# Sheet3-multi.net
KiCad netlist of a schematic drawn in Altium Designer
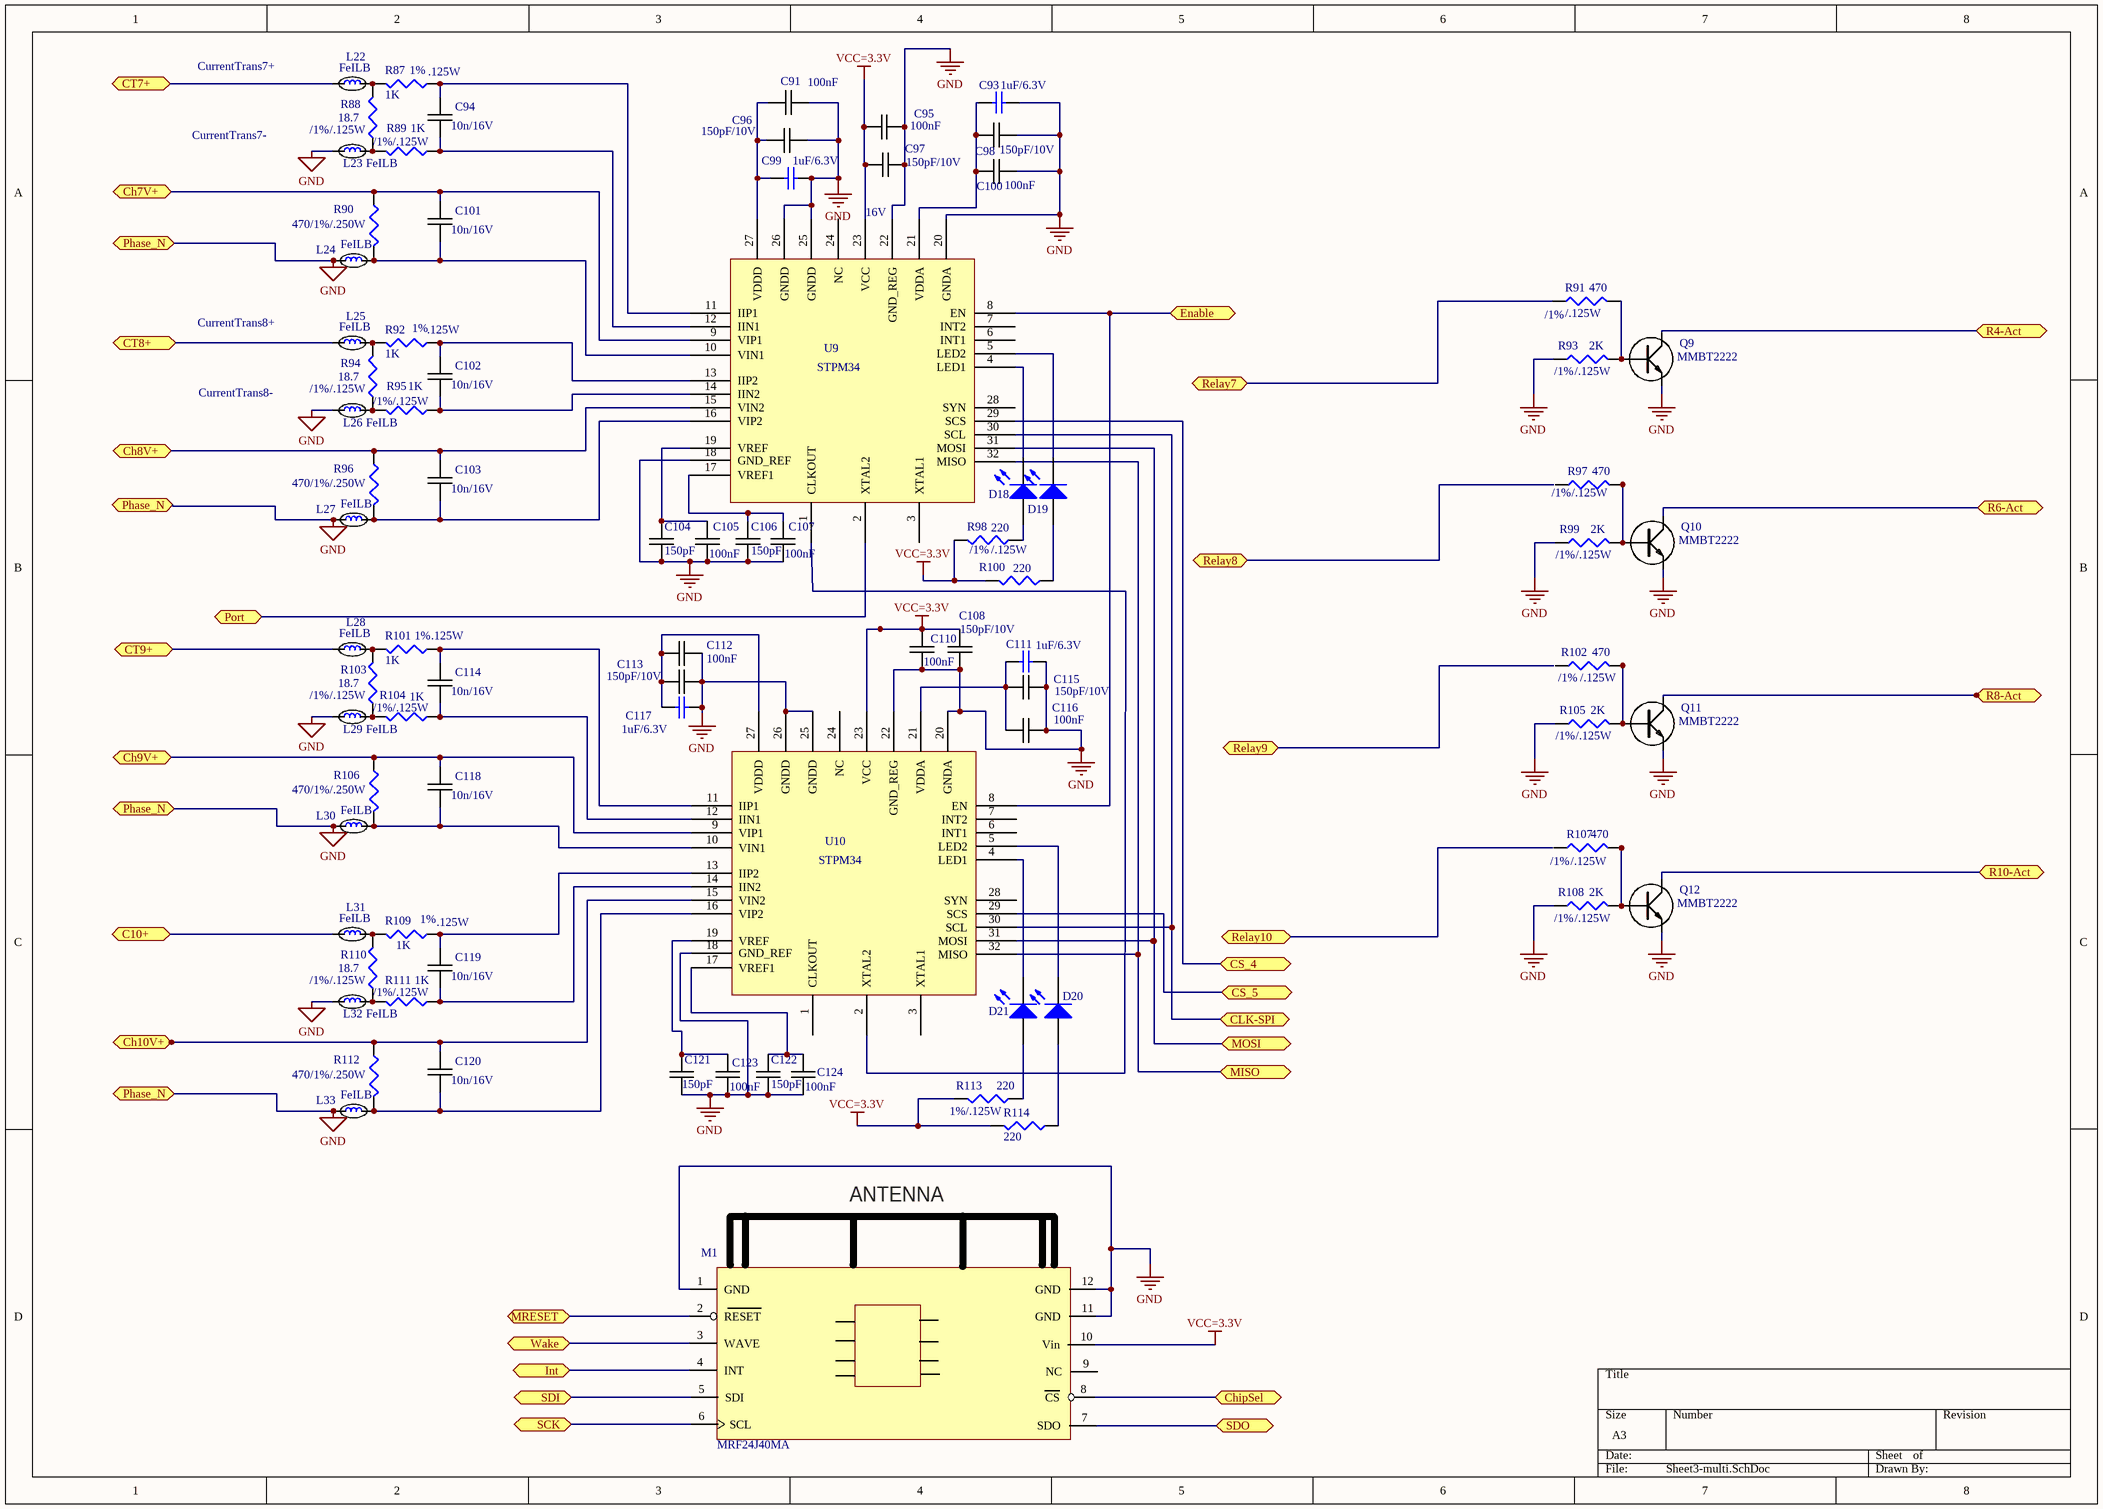
[diagram p0: Sheet3-multi.SchDoc]

(export (version "E")
  (design (tool "Eeschema 10.0.6"))
  (components
    (comp (ref "C91")
      (value "100nF")
      (footprint "0402C-GENERIC")
      (description "CAPACITOR 0805 CERAMIC")
      (fields (field (name "MANUFACTURER") "Taiyo Yuden"))
      (libsource (lib "vh_altium_library") (part "0805C-18PF-50V-C0G-JOH"))
    )
    (comp (ref "C93")
      (value "1uF/6.3V")
      (footprint "0402C-GENERIC")
      (description "Capacitor")
      (fields (field (name "MANUFACTURER") "Murata") (field (name "PUBLISHER") "Altium Limited"))
      (libsource (lib "Miscellaneous Devices") (part "Cap"))
    )
    (comp (ref "C94")
      (value "10n/16V")
      (footprint "0402C-GENERIC")
      (description "CAPACITOR 0805 CERAMIC")
      (fields (field (name "MANUFACTURER") "Murata Electronics"))
      (libsource (lib "vh_altium_library") (part "0805C-18PF-50V-C0G-JOH"))
    )
    (comp (ref "C95")
      (value "100nF")
      (footprint "0402C-GENERIC")
      (description "CAPACITOR 0805 CERAMIC")
      (fields (field (name "MANUFACTURER") "Taiyo Yuden"))
      (libsource (lib "vh_altium_library") (part "0805C-18PF-50V-C0G-JOH"))
    )
    (comp (ref "C96")
      (value "150pF/10V")
      (footprint "0402C-GENERIC")
      (description "CAPACITOR 0805 CERAMIC")
      (fields (field (name "MANUFACTURER") "Wurth Electronics"))
      (libsource (lib "vh_altium_library") (part "0805C-18PF-50V-C0G-JOH"))
    )
    (comp (ref "C97")
      (value "150pF/10V")
      (footprint "0402C-GENERIC")
      (description "CAPACITOR 0805 CERAMIC")
      (fields (field (name "MANUFACTURER") "Wurth Electronics"))
      (libsource (lib "vh_altium_library") (part "0805C-18PF-50V-C0G-JOH"))
    )
    (comp (ref "C98")
      (value "150pF/10V")
      (footprint "0402C-GENERIC")
      (description "CAPACITOR 0805 CERAMIC")
      (fields (field (name "MANUFACTURER") "Wurth Electronics"))
      (libsource (lib "vh_altium_library") (part "0805C-18PF-50V-C0G-JOH"))
    )
    (comp (ref "C99")
      (value "1uF/6.3V")
      (footprint "0402C-GENERIC")
      (description "Capacitor")
      (fields (field (name "MANUFACTURER") "Murata") (field (name "PUBLISHER") "Altium Limited"))
      (libsource (lib "Miscellaneous Devices") (part "Cap"))
    )
    (comp (ref "C100")
      (value "100nF")
      (footprint "0402C-GENERIC")
      (description "CAPACITOR 0805 CERAMIC")
      (fields (field (name "MANUFACTURER") "Taiyo Yuden"))
      (libsource (lib "vh_altium_library") (part "0805C-18PF-50V-C0G-JOH"))
    )
    (comp (ref "C101")
      (value "10n/16V")
      (footprint "0402C-GENERIC")
      (description "CAPACITOR 0805 CERAMIC")
      (fields (field (name "MANUFACTURER") "Murata Electronics"))
      (libsource (lib "vh_altium_library") (part "0805C-18PF-50V-C0G-JOH"))
    )
    (comp (ref "C102")
      (value "10n/16V")
      (footprint "0402C-GENERIC")
      (description "CAPACITOR 0805 CERAMIC")
      (fields (field (name "MANUFACTURER") "Murata Electronics"))
      (libsource (lib "vh_altium_library") (part "0805C-18PF-50V-C0G-JOH"))
    )
    (comp (ref "C103")
      (value "10n/16V")
      (footprint "0402C-GENERIC")
      (description "CAPACITOR 0805 CERAMIC")
      (fields (field (name "MANUFACTURER") "Murata Electronics"))
      (libsource (lib "vh_altium_library") (part "0805C-18PF-50V-C0G-JOH"))
    )
    (comp (ref "C104")
      (value "150pF")
      (footprint "0402C-GENERIC")
      (description "CAPACITOR 0805 CERAMIC")
      (fields (field (name "MANUFACTURER") "Wurth Electronics"))
      (libsource (lib "vh_altium_library") (part "0805C-18PF-50V-C0G-JOH"))
    )
    (comp (ref "C105")
      (value "100nF")
      (footprint "0402C-GENERIC")
      (description "CAPACITOR 0805 CERAMIC")
      (fields (field (name "MANUFACTURER") "Taiyo Yuden"))
      (libsource (lib "vh_altium_library") (part "0805C-18PF-50V-C0G-JOH"))
    )
    (comp (ref "C106")
      (value "150pF")
      (footprint "0402C-GENERIC")
      (description "CAPACITOR 0805 CERAMIC")
      (fields (field (name "MANUFACTURER") "Wurth Electronics"))
      (libsource (lib "vh_altium_library") (part "0805C-18PF-50V-C0G-JOH"))
    )
    (comp (ref "C107")
      (value "100nF")
      (footprint "0402C-GENERIC")
      (description "CAPACITOR 0805 CERAMIC")
      (fields (field (name "MANUFACTURER") "Taiyo Yuden"))
      (libsource (lib "vh_altium_library") (part "0805C-18PF-50V-C0G-JOH"))
    )
    (comp (ref "C108")
      (value "150pF/10V")
      (footprint "0402C-GENERIC")
      (description "CAPACITOR 0805 CERAMIC")
      (fields (field (name "MANUFACTURER") "Wurth Electronics"))
      (libsource (lib "vh_altium_library") (part "0805C-18PF-50V-C0G-JOH"))
    )
    (comp (ref "C110")
      (value "100nF")
      (footprint "0402C-GENERIC")
      (description "CAPACITOR 0805 CERAMIC")
      (fields (field (name "MANUFACTURER") "Taiyo Yuden"))
      (libsource (lib "vh_altium_library") (part "0805C-18PF-50V-C0G-JOH"))
    )
    (comp (ref "C111")
      (value "1uF/6.3V")
      (footprint "0402C-GENERIC")
      (description "Capacitor")
      (fields (field (name "MANUFACTURER") "Murata") (field (name "PUBLISHER") "Altium Limited"))
      (libsource (lib "Miscellaneous Devices") (part "Cap"))
    )
    (comp (ref "C112")
      (value "100nF")
      (footprint "0402C-GENERIC")
      (description "CAPACITOR 0805 CERAMIC")
      (fields (field (name "MANUFACTURER") "Taiyo Yuden"))
      (libsource (lib "vh_altium_library") (part "0805C-18PF-50V-C0G-JOH"))
    )
    (comp (ref "C113")
      (value "150pF/10V")
      (footprint "0402C-GENERIC")
      (description "CAPACITOR 0805 CERAMIC")
      (fields (field (name "MANUFACTURER") "Wurth Electronics"))
      (libsource (lib "vh_altium_library") (part "0805C-18PF-50V-C0G-JOH"))
    )
    (comp (ref "C114")
      (value "10n/16V")
      (footprint "0402C-GENERIC")
      (description "CAPACITOR 0805 CERAMIC")
      (fields (field (name "MANUFACTURER") "Murata Electronics"))
      (libsource (lib "vh_altium_library") (part "0805C-18PF-50V-C0G-JOH"))
    )
    (comp (ref "C115")
      (value "150pF/10V")
      (footprint "0402C-GENERIC")
      (description "CAPACITOR 0805 CERAMIC")
      (fields (field (name "MANUFACTURER") "Wurth Electronics"))
      (libsource (lib "vh_altium_library") (part "0805C-18PF-50V-C0G-JOH"))
    )
    (comp (ref "C116")
      (value "100nF")
      (footprint "0402C-GENERIC")
      (description "CAPACITOR 0805 CERAMIC")
      (fields (field (name "MANUFACTURER") "Taiyo Yuden"))
      (libsource (lib "vh_altium_library") (part "0805C-18PF-50V-C0G-JOH"))
    )
    (comp (ref "C117")
      (value "1uF/6.3V")
      (footprint "0402C-GENERIC")
      (description "Capacitor")
      (fields (field (name "MANUFACTURER") "Murata") (field (name "PUBLISHER") "Altium Limited"))
      (libsource (lib "Miscellaneous Devices") (part "Cap"))
    )
    (comp (ref "C118")
      (value "10n/16V")
      (footprint "0402C-GENERIC")
      (description "CAPACITOR 0805 CERAMIC")
      (fields (field (name "MANUFACTURER") "Murata Electronics"))
      (libsource (lib "vh_altium_library") (part "0805C-18PF-50V-C0G-JOH"))
    )
    (comp (ref "C119")
      (value "10n/16V")
      (footprint "0402C-GENERIC")
      (description "CAPACITOR 0805 CERAMIC")
      (fields (field (name "MANUFACTURER") "Murata Electronics"))
      (libsource (lib "vh_altium_library") (part "0805C-18PF-50V-C0G-JOH"))
    )
    (comp (ref "C120")
      (value "10n/16V")
      (footprint "0402C-GENERIC")
      (description "CAPACITOR 0805 CERAMIC")
      (fields (field (name "MANUFACTURER") "Murata Electronics"))
      (libsource (lib "vh_altium_library") (part "0805C-18PF-50V-C0G-JOH"))
    )
    (comp (ref "C121")
      (value "150pF")
      (footprint "0402C-GENERIC")
      (description "CAPACITOR 0805 CERAMIC")
      (fields (field (name "MANUFACTURER") "Wurth Electronics"))
      (libsource (lib "vh_altium_library") (part "0805C-18PF-50V-C0G-JOH"))
    )
    (comp (ref "C122")
      (value "150pF")
      (footprint "0402C-GENERIC")
      (description "CAPACITOR 0805 CERAMIC")
      (fields (field (name "MANUFACTURER") "Wurth Electronics"))
      (libsource (lib "vh_altium_library") (part "0805C-18PF-50V-C0G-JOH"))
    )
    (comp (ref "C123")
      (value "100nF")
      (footprint "0402C-GENERIC")
      (description "CAPACITOR 0805 CERAMIC")
      (fields (field (name "MANUFACTURER") "Taiyo Yuden"))
      (libsource (lib "vh_altium_library") (part "0805C-18PF-50V-C0G-JOH"))
    )
    (comp (ref "C124")
      (value "100nF")
      (footprint "0402C-GENERIC")
      (description "CAPACITOR 0805 CERAMIC")
      (fields (field (name "MANUFACTURER") "Taiyo Yuden"))
      (libsource (lib "vh_altium_library") (part "0805C-18PF-50V-C0G-JOH"))
    )
    (comp (ref "D18")
      (value "LED2")
      (footprint "LED-SM")
      (description "Typical RED, GREEN, YELLOW, AMBER GaAs LED")
      (fields (field (name "MANUFACTURER") "Lite-On Inc") (field (name "PUBLISHER") "Altium Limited"))
      (libsource (lib "Miscellaneous Devices") (part "LED2"))
    )
    (comp (ref "D19")
      (value "LED2")
      (footprint "LED-SM")
      (description "Typical RED, GREEN, YELLOW, AMBER GaAs LED")
      (fields (field (name "MANUFACTURER") "Lite-On Inc") (field (name "PUBLISHER") "Altium Limited"))
      (libsource (lib "Miscellaneous Devices") (part "LED2"))
    )
    (comp (ref "D20")
      (value "LED2")
      (footprint "LED-SM")
      (description "Typical RED, GREEN, YELLOW, AMBER GaAs LED")
      (fields (field (name "MANUFACTURER") "Lite-On Inc") (field (name "PUBLISHER") "Altium Limited"))
      (libsource (lib "Miscellaneous Devices") (part "LED2"))
    )
    (comp (ref "D21")
      (value "LED2")
      (footprint "LED-SM")
      (description "Typical RED, GREEN, YELLOW, AMBER GaAs LED")
      (fields (field (name "MANUFACTURER") "Lite-On Inc") (field (name "PUBLISHER") "Altium Limited"))
      (libsource (lib "Miscellaneous Devices") (part "LED2"))
    )
    (comp (ref "L22")
      (value "FeILB")
      (footprint "0603C-TBD")
      (fields (field (name "MANUFACTURER") "Brand Samsung"))
      (libsource (lib "SMLib") (part "FerrBeads/ILBB"))
    )
    (comp (ref "L23")
      (value "FeILB")
      (footprint "0603C-TBD")
      (fields (field (name "MANUFACTURER") "Brand Samsung"))
      (libsource (lib "SMLib") (part "FerrBeads/ILBB"))
    )
    (comp (ref "L24")
      (value "FeILB")
      (footprint "0603C-TBD")
      (fields (field (name "MANUFACTURER") "Brand Samsung"))
      (libsource (lib "SMLib") (part "FerrBeads/ILBB"))
    )
    (comp (ref "L25")
      (value "FeILB")
      (footprint "0603C-TBD")
      (fields (field (name "MANUFACTURER") "Brand Samsung"))
      (libsource (lib "SMLib") (part "FerrBeads/ILBB"))
    )
    (comp (ref "L26")
      (value "FeILB")
      (footprint "0603C-TBD")
      (fields (field (name "MANUFACTURER") "Brand Samsung"))
      (libsource (lib "SMLib") (part "FerrBeads/ILBB"))
    )
    (comp (ref "L27")
      (value "FeILB")
      (footprint "0603C-TBD")
      (fields (field (name "MANUFACTURER") "Brand Samsung"))
      (libsource (lib "SMLib") (part "FerrBeads/ILBB"))
    )
    (comp (ref "L28")
      (value "FeILB")
      (footprint "0603C-TBD")
      (fields (field (name "MANUFACTURER") "Brand Samsung"))
      (libsource (lib "SMLib") (part "FerrBeads/ILBB"))
    )
    (comp (ref "L29")
      (value "FeILB")
      (footprint "0603C-TBD")
      (fields (field (name "MANUFACTURER") "Brand Samsung"))
      (libsource (lib "SMLib") (part "FerrBeads/ILBB"))
    )
    (comp (ref "L30")
      (value "FeILB")
      (footprint "0603C-TBD")
      (fields (field (name "MANUFACTURER") "Brand Samsung"))
      (libsource (lib "SMLib") (part "FerrBeads/ILBB"))
    )
    (comp (ref "L31")
      (value "FeILB")
      (footprint "0603C-TBD")
      (fields (field (name "MANUFACTURER") "Brand Samsung"))
      (libsource (lib "SMLib") (part "FerrBeads/ILBB"))
    )
    (comp (ref "L32")
      (value "FeILB")
      (footprint "0603C-TBD")
      (fields (field (name "MANUFACTURER") "Brand Samsung"))
      (libsource (lib "SMLib") (part "FerrBeads/ILBB"))
    )
    (comp (ref "L33")
      (value "FeILB")
      (footprint "0603C-TBD")
      (fields (field (name "MANUFACTURER") "Brand Samsung"))
      (libsource (lib "SMLib") (part "FerrBeads/ILBB"))
    )
    (comp (ref "M1")
      (value "MRF24J40MA")
      (footprint "MRF24J40MA-zigBEE module")
      (fields (field (name "MANUFACTURER") "Microchip"))
      (libsource (lib "SMLib") (part "MRF24J40MA"))
    )
    (comp (ref "Q9")
      (value "MMBT2222")
      (footprint "MMBT2222")
      (description "BC847 SMALL SIGNAL NPN TRANSISTOR")
      (fields (field (name "MANUFACTURER") "Diodes  Inc."))
      (libsource (lib "vh_altium_library") (part "MMBT2222"))
    )
    (comp (ref "Q10")
      (value "MMBT2222")
      (footprint "MMBT2222")
      (description "BC847 SMALL SIGNAL NPN TRANSISTOR")
      (fields (field (name "MANUFACTURER") "Diodes  Inc."))
      (libsource (lib "vh_altium_library") (part "MMBT2222"))
    )
    (comp (ref "Q11")
      (value "MMBT2222")
      (footprint "MMBT2222")
      (description "BC847 SMALL SIGNAL NPN TRANSISTOR")
      (fields (field (name "MANUFACTURER") "Diodes  Inc."))
      (libsource (lib "vh_altium_library") (part "MMBT2222"))
    )
    (comp (ref "Q12")
      (value "MMBT2222")
      (footprint "MMBT2222")
      (description "BC847 SMALL SIGNAL NPN TRANSISTOR")
      (fields (field (name "MANUFACTURER") "Diodes  Inc."))
      (libsource (lib "vh_altium_library") (part "MMBT2222"))
    )
    (comp (ref "R87")
      (value "1K")
      (footprint "0402R-TBD")
      (description "Resistor")
      (fields (field (name "MANUFACTURER") "Panasonic") (field (name "PUBLISHER") "Altium Limited"))
      (libsource (lib "Miscellaneous Devices") (part "Res3"))
    )
    (comp (ref "R88")
      (value "18.7")
      (footprint "0402R-TBD")
      (description "Resistor")
      (fields (field (name "MANUFACTURER") "Panasonic") (field (name "PUBLISHER") "Altium Limited"))
      (libsource (lib "Miscellaneous Devices") (part "Res3"))
    )
    (comp (ref "R89")
      (value "1K")
      (footprint "0402R-TBD")
      (description "Resistor")
      (fields (field (name "MANUFACTURER") "Panasonic") (field (name "PUBLISHER") "Altium Limited"))
      (libsource (lib "Miscellaneous Devices") (part "Res3"))
    )
    (comp (ref "R90")
      (value "470/1%/.250W")
      (footprint "1206FB-GENERIC")
      (description "Resistor")
      (fields (field (name "MANUFACTURER") "Panasonic Co") (field (name "PUBLISHER") "Altium Limited"))
      (libsource (lib "Miscellaneous Devices") (part "Res3"))
    )
    (comp (ref "R91")
      (value "470")
      (footprint "0402R-TBD")
      (description "Resistor")
      (fields (field (name "MANUFACTURER") "Panasonic") (field (name "PUBLISHER") "Altium Limited"))
      (libsource (lib "Miscellaneous Devices") (part "Res3"))
    )
    (comp (ref "R92")
      (value "1K")
      (footprint "0402R-TBD")
      (description "Resistor")
      (fields (field (name "MANUFACTURER") "Panasonic") (field (name "PUBLISHER") "Altium Limited"))
      (libsource (lib "Miscellaneous Devices") (part "Res3"))
    )
    (comp (ref "R93")
      (value "2K")
      (footprint "0402R-TBD")
      (description "Resistor")
      (fields (field (name "MANUFACTURER") "Panasonic") (field (name "PUBLISHER") "Altium Limited"))
      (libsource (lib "Miscellaneous Devices") (part "Res3"))
    )
    (comp (ref "R94")
      (value "18.7")
      (footprint "0402R-TBD")
      (description "Resistor")
      (fields (field (name "MANUFACTURER") "Panasonic") (field (name "PUBLISHER") "Altium Limited"))
      (libsource (lib "Miscellaneous Devices") (part "Res3"))
    )
    (comp (ref "R95")
      (value "1K")
      (footprint "0402R-TBD")
      (description "Resistor")
      (fields (field (name "MANUFACTURER") "Panasonic") (field (name "PUBLISHER") "Altium Limited"))
      (libsource (lib "Miscellaneous Devices") (part "Res3"))
    )
    (comp (ref "R96")
      (value "470/1%/.250W")
      (footprint "1206FB-GENERIC")
      (description "Resistor")
      (fields (field (name "MANUFACTURER") "Panasonic Co") (field (name "PUBLISHER") "Altium Limited"))
      (libsource (lib "Miscellaneous Devices") (part "Res3"))
    )
    (comp (ref "R97")
      (value "470")
      (footprint "0402R-TBD")
      (description "Resistor")
      (fields (field (name "MANUFACTURER") "Panasonic") (field (name "PUBLISHER") "Altium Limited"))
      (libsource (lib "Miscellaneous Devices") (part "Res3"))
    )
    (comp (ref "R98")
      (value "220")
      (footprint "0402C-TBD")
      (description "Resistor")
      (fields (field (name "MANUFACTURER") "Panasonic") (field (name "PUBLISHER") "Altium Limited"))
      (libsource (lib "Miscellaneous Devices") (part "Res3"))
    )
    (comp (ref "R99")
      (value "2K")
      (footprint "0402R-TBD")
      (description "Resistor")
      (fields (field (name "MANUFACTURER") "Panasonic") (field (name "PUBLISHER") "Altium Limited"))
      (libsource (lib "Miscellaneous Devices") (part "Res3"))
    )
    (comp (ref "R100")
      (value "220")
      (footprint "0402C-TBD")
      (description "Resistor")
      (fields (field (name "MANUFACTURER") "Panasonic") (field (name "PUBLISHER") "Altium Limited"))
      (libsource (lib "Miscellaneous Devices") (part "Res3"))
    )
    (comp (ref "R101")
      (value "1K")
      (footprint "0402R-TBD")
      (description "Resistor")
      (fields (field (name "MANUFACTURER") "Panasonic") (field (name "PUBLISHER") "Altium Limited"))
      (libsource (lib "Miscellaneous Devices") (part "Res3"))
    )
    (comp (ref "R102")
      (value "470")
      (footprint "0402R-TBD")
      (description "Resistor")
      (fields (field (name "MANUFACTURER") "Panasonic") (field (name "PUBLISHER") "Altium Limited"))
      (libsource (lib "Miscellaneous Devices") (part "Res3"))
    )
    (comp (ref "R103")
      (value "18.7")
      (footprint "0402R-TBD")
      (description "Resistor")
      (fields (field (name "MANUFACTURER") "Panasonic") (field (name "PUBLISHER") "Altium Limited"))
      (libsource (lib "Miscellaneous Devices") (part "Res3"))
    )
    (comp (ref "R104")
      (value "1K")
      (footprint "0402R-TBD")
      (description "Resistor")
      (fields (field (name "MANUFACTURER") "Panasonic") (field (name "PUBLISHER") "Altium Limited"))
      (libsource (lib "Miscellaneous Devices") (part "Res3"))
    )
    (comp (ref "R105")
      (value "2K")
      (footprint "0402R-TBD")
      (description "Resistor")
      (fields (field (name "MANUFACTURER") "Panasonic") (field (name "PUBLISHER") "Altium Limited"))
      (libsource (lib "Miscellaneous Devices") (part "Res3"))
    )
    (comp (ref "R106")
      (value "470/1%/.250W")
      (footprint "1206FB-GENERIC")
      (description "Resistor")
      (fields (field (name "MANUFACTURER") "Panasonic Co") (field (name "PUBLISHER") "Altium Limited"))
      (libsource (lib "Miscellaneous Devices") (part "Res3"))
    )
    (comp (ref "R107")
      (value "470")
      (footprint "0402R-TBD")
      (description "Resistor")
      (fields (field (name "MANUFACTURER") "Panasonic") (field (name "PUBLISHER") "Altium Limited"))
      (libsource (lib "Miscellaneous Devices") (part "Res3"))
    )
    (comp (ref "R108")
      (value "2K")
      (footprint "0402R-TBD")
      (description "Resistor")
      (fields (field (name "MANUFACTURER") "Panasonic") (field (name "PUBLISHER") "Altium Limited"))
      (libsource (lib "Miscellaneous Devices") (part "Res3"))
    )
    (comp (ref "R109")
      (value "1K")
      (footprint "0402R-TBD")
      (description "Resistor")
      (fields (field (name "MANUFACTURER") "Panasonic") (field (name "PUBLISHER") "Altium Limited"))
      (libsource (lib "Miscellaneous Devices") (part "Res3"))
    )
    (comp (ref "R110")
      (value "18.7")
      (footprint "0402R-TBD")
      (description "Resistor")
      (fields (field (name "MANUFACTURER") "Panasonic") (field (name "PUBLISHER") "Altium Limited"))
      (libsource (lib "Miscellaneous Devices") (part "Res3"))
    )
    (comp (ref "R111")
      (value "1K")
      (footprint "0402R-TBD")
      (description "Resistor")
      (fields (field (name "MANUFACTURER") "Panasonic") (field (name "PUBLISHER") "Altium Limited"))
      (libsource (lib "Miscellaneous Devices") (part "Res3"))
    )
    (comp (ref "R112")
      (value "470/1%/.250W")
      (footprint "1206FB-GENERIC")
      (description "Resistor")
      (fields (field (name "MANUFACTURER") "Panasonic Co") (field (name "PUBLISHER") "Altium Limited"))
      (libsource (lib "Miscellaneous Devices") (part "Res3"))
    )
    (comp (ref "R113")
      (value "220")
      (footprint "0402C-TBD")
      (description "Resistor")
      (fields (field (name "MANUFACTURER") "Panasonic") (field (name "PUBLISHER") "Altium Limited"))
      (libsource (lib "Miscellaneous Devices") (part "Res3"))
    )
    (comp (ref "R114")
      (value "220")
      (footprint "0402C-TBD")
      (description "Resistor")
      (fields (field (name "MANUFACTURER") "Panasonic") (field (name "PUBLISHER") "Altium Limited"))
      (libsource (lib "Miscellaneous Devices") (part "Res3"))
    )
    (comp (ref "U9")
      (value "STPM34")
      (footprint "32M1-A_L")
      (fields (field (name "MANUFACTURER") "STMicroelectronic"))
      (libsource (lib "SMLib") (part "STPM34"))
    )
    (comp (ref "U10")
      (value "STPM34")
      (footprint "32M1-A_L")
      (fields (field (name "MANUFACTURER") "STMicroelectronic"))
      (libsource (lib "SMLib") (part "STPM34"))
    )
  )
  (nets
    (net (code "1") (name "/C10+") (class "Default")
      (node (ref "L31") (pin "1") (pinfunction "1_1") (pintype "passive"))
    )
    (net (code "2") (name "/CLK-SPI") (class "Default")
      (node (ref "U10") (pin "30") (pinfunction "SCL_30") (pintype "passive"))
      (node (ref "U9") (pin "30") (pinfunction "SCL_30") (pintype "passive"))
    )
    (net (code "3") (name "/CS_4") (class "Default")
      (node (ref "U9") (pin "29") (pinfunction "SCS_29") (pintype "passive"))
    )
    (net (code "4") (name "/CS_5") (class "Default")
      (node (ref "U10") (pin "29") (pinfunction "SCS_29") (pintype "passive"))
    )
    (net (code "5") (name "/CT7+") (class "Default")
      (node (ref "L22") (pin "1") (pinfunction "1_1") (pintype "passive"))
    )
    (net (code "6") (name "/CT8+") (class "Default")
      (node (ref "L25") (pin "1") (pinfunction "1_1") (pintype "passive"))
    )
    (net (code "7") (name "/CT9+") (class "Default")
      (node (ref "L28") (pin "1") (pinfunction "1_1") (pintype "passive"))
    )
    (net (code "8") (name "/Ch7V+") (class "Default")
      (node (ref "C101") (pin "2") (pintype "passive"))
      (node (ref "R90") (pin "1") (pinfunction "1_1") (pintype "passive"))
      (node (ref "U9") (pin "9") (pinfunction "VIP1_9") (pintype "passive"))
    )
    (net (code "9") (name "/Ch8V+") (class "Default")
      (node (ref "C103") (pin "2") (pintype "passive"))
      (node (ref "R96") (pin "1") (pinfunction "1_1") (pintype "passive"))
      (node (ref "U9") (pin "15") (pinfunction "VIN2_15") (pintype "passive"))
    )
    (net (code "10") (name "/Ch9V+") (class "Default")
      (node (ref "C118") (pin "2") (pintype "passive"))
      (node (ref "R106") (pin "1") (pinfunction "1_1") (pintype "passive"))
      (node (ref "U10") (pin "9") (pinfunction "VIP1_9") (pintype "passive"))
    )
    (net (code "11") (name "/Ch10V+") (class "Default")
      (node (ref "C120") (pin "2") (pintype "passive"))
      (node (ref "R112") (pin "1") (pinfunction "1_1") (pintype "passive"))
      (node (ref "U10") (pin "15") (pinfunction "VIN2_15") (pintype "passive"))
    )
    (net (code "12") (name "/ChipSel") (class "Default")
      (node (ref "M1") (pin "8") (pinfunction "CS_8") (pintype "passive"))
    )
    (net (code "13") (name "/Enable") (class "Default")
      (node (ref "U10") (pin "8") (pinfunction "EN_8") (pintype "passive"))
      (node (ref "U9") (pin "8") (pinfunction "EN_8") (pintype "passive"))
    )
    (net (code "14") (name "/Int") (class "Default")
      (node (ref "M1") (pin "4") (pinfunction "INT_4") (pintype "passive"))
    )
    (net (code "15") (name "/MISO") (class "Default")
      (node (ref "U10") (pin "32") (pinfunction "MISO_32") (pintype "passive"))
      (node (ref "U9") (pin "32") (pinfunction "MISO_32") (pintype "passive"))
    )
    (net (code "16") (name "/MOSI") (class "Default")
      (node (ref "U10") (pin "31") (pinfunction "MOSI_31") (pintype "passive"))
      (node (ref "U9") (pin "31") (pinfunction "MOSI_31") (pintype "passive"))
    )
    (net (code "17") (name "/MRESET") (class "Default")
      (node (ref "M1") (pin "2") (pinfunction "RESET_2") (pintype "passive"))
    )
    (net (code "18") (name "/Port") (class "Default")
      (node (ref "U9") (pin "2") (pinfunction "XTAL2_2") (pintype "passive"))
    )
    (net (code "19") (name "/R4-Act") (class "Default") (node (ref "Q9") (pin "C") (pintype "passive")))
    (net (code "20") (name "/R6-Act") (class "Default") (node (ref "Q10") (pin "C") (pintype "passive")))
    (net (code "21") (name "/R8-Act") (class "Default") (node (ref "Q11") (pin "C") (pintype "passive")))
    (net (code "22") (name "/R10-Act") (class "Default") (node (ref "Q12") (pin "C") (pintype "passive")))
    (net (code "23") (name "/Relay7") (class "Default")
      (node (ref "R91") (pin "1") (pinfunction "1_1") (pintype "passive"))
    )
    (net (code "27") (name "/SCK") (class "Default")
      (node (ref "M1") (pin "6") (pinfunction "SCL_6") (pintype "passive"))
    )
    (net (code "28") (name "/SDI") (class "Default")
      (node (ref "M1") (pin "5") (pinfunction "SDI_5") (pintype "passive"))
    )
    (net (code "29") (name "/SDO") (class "Default")
      (node (ref "M1") (pin "7") (pinfunction "SDO_7") (pintype "passive"))
    )
    (net (code "30") (name "/Wake") (class "Default")
      (node (ref "M1") (pin "3") (pinfunction "WAVE_3") (pintype "passive"))
    )
    (net (code "31") (name "GND") (class "Default")
      (node (ref "C100") (pin "2") (pintype "passive"))
      (node (ref "C104") (pin "2") (pintype "passive"))
      (node (ref "C105") (pin "2") (pintype "passive"))
      (node (ref "C106") (pin "2") (pintype "passive"))
      (node (ref "C107") (pin "2") (pintype "passive"))
      (node (ref "C108") (pin "2") (pintype "passive"))
      (node (ref "C110") (pin "2") (pintype "passive"))
      (node (ref "C111") (pin "2") (pinfunction "2_2") (pintype "passive"))
      (node (ref "C112") (pin "2") (pintype "passive"))
      (node (ref "C113") (pin "2") (pintype "passive"))
      (node (ref "C115") (pin "2") (pintype "passive"))
      (node (ref "C116") (pin "2") (pintype "passive"))
      (node (ref "C117") (pin "2") (pinfunction "2_2") (pintype "passive"))
      (node (ref "C121") (pin "2") (pintype "passive"))
      (node (ref "C122") (pin "2") (pintype "passive"))
      (node (ref "C123") (pin "2") (pintype "passive"))
      (node (ref "C124") (pin "2") (pintype "passive"))
      (node (ref "C91") (pin "2") (pintype "passive"))
      (node (ref "C93") (pin "2") (pinfunction "2_2") (pintype "passive"))
      (node (ref "C95") (pin "2") (pintype "passive"))
      (node (ref "C96") (pin "2") (pintype "passive"))
      (node (ref "C97") (pin "2") (pintype "passive"))
      (node (ref "C98") (pin "1") (pintype "passive"))
      (node (ref "C99") (pin "2") (pinfunction "2_2") (pintype "passive"))
      (node (ref "L23") (pin "1") (pinfunction "1_1") (pintype "passive"))
      (node (ref "L24") (pin "1") (pinfunction "1_1") (pintype "passive"))
      (node (ref "L26") (pin "1") (pinfunction "1_1") (pintype "passive"))
      (node (ref "L27") (pin "1") (pinfunction "1_1") (pintype "passive"))
      (node (ref "L29") (pin "1") (pinfunction "1_1") (pintype "passive"))
      (node (ref "L30") (pin "1") (pinfunction "1_1") (pintype "passive"))
      (node (ref "L32") (pin "1") (pinfunction "1_1") (pintype "passive"))
      (node (ref "L33") (pin "1") (pinfunction "1_1") (pintype "passive"))
      (node (ref "M1") (pin "1") (pinfunction "GND_1") (pintype "passive"))
      (node (ref "M1") (pin "11") (pinfunction "GND_11") (pintype "passive"))
      (node (ref "M1") (pin "12") (pinfunction "GND_12") (pintype "passive"))
      (node (ref "Q10") (pin "E") (pintype "passive"))
      (node (ref "Q11") (pin "E") (pintype "passive"))
      (node (ref "Q12") (pin "E") (pintype "passive"))
      (node (ref "Q9") (pin "E") (pintype "passive"))
      (node (ref "R105") (pin "1") (pinfunction "1_1") (pintype "passive"))
      (node (ref "R108") (pin "1") (pinfunction "1_1") (pintype "passive"))
      (node (ref "R93") (pin "1") (pinfunction "1_1") (pintype "passive"))
      (node (ref "R99") (pin "1") (pinfunction "1_1") (pintype "passive"))
      (node (ref "U10") (pin "18") (pinfunction "GND_REF_18") (pintype "passive"))
      (node (ref "U10") (pin "20") (pinfunction "GNDA_20") (pintype "passive"))
      (node (ref "U10") (pin "22") (pinfunction "GND_REG_22") (pintype "passive"))
      (node (ref "U10") (pin "25") (pinfunction "GNDD_25") (pintype "passive"))
      (node (ref "U10") (pin "26") (pinfunction "GNDD_26") (pintype "passive"))
      (node (ref "U9") (pin "18") (pinfunction "GND_REF_18") (pintype "passive"))
      (node (ref "U9") (pin "20") (pinfunction "GNDA_20") (pintype "passive"))
      (node (ref "U9") (pin "22") (pinfunction "GND_REG_22") (pintype "passive"))
      (node (ref "U9") (pin "25") (pinfunction "GNDD_25") (pintype "passive"))
      (node (ref "U9") (pin "26") (pinfunction "GNDD_26") (pintype "passive"))
    )
    (net (code "32") (name "Net-(D18-A)") (class "Default")
      (node (ref "D18") (pin "1") (pinfunction "A_1") (pintype "passive"))
      (node (ref "R98") (pin "1") (pinfunction "1_1") (pintype "passive"))
    )
    (net (code "33") (name "Net-(D18-K)") (class "Default")
      (node (ref "D18") (pin "2") (pinfunction "K_2") (pintype "passive"))
      (node (ref "U9") (pin "4") (pinfunction "LED1_4") (pintype "passive"))
    )
    (net (code "34") (name "Net-(D19-A)") (class "Default")
      (node (ref "D19") (pin "1") (pinfunction "A_1") (pintype "passive"))
      (node (ref "R100") (pin "1") (pinfunction "1_1") (pintype "passive"))
    )
    (net (code "35") (name "Net-(D19-K)") (class "Default")
      (node (ref "D19") (pin "2") (pinfunction "K_2") (pintype "passive"))
      (node (ref "U9") (pin "5") (pinfunction "LED2_5") (pintype "passive"))
    )
    (net (code "36") (name "Net-(D20-A)") (class "Default")
      (node (ref "D20") (pin "1") (pinfunction "A_1") (pintype "passive"))
      (node (ref "R114") (pin "1") (pinfunction "1_1") (pintype "passive"))
    )
    (net (code "37") (name "Net-(D20-K)") (class "Default")
      (node (ref "D20") (pin "2") (pinfunction "K_2") (pintype "passive"))
      (node (ref "U10") (pin "5") (pinfunction "LED2_5") (pintype "passive"))
    )
    (net (code "38") (name "Net-(D21-A)") (class "Default")
      (node (ref "D21") (pin "1") (pinfunction "A_1") (pintype "passive"))
      (node (ref "R113") (pin "1") (pinfunction "1_1") (pintype "passive"))
    )
    (net (code "39") (name "Net-(D21-K)") (class "Default")
      (node (ref "D21") (pin "2") (pinfunction "K_2") (pintype "passive"))
      (node (ref "U10") (pin "4") (pinfunction "LED1_4") (pintype "passive"))
    )
    (net (code "40") (name "Net-(L22-Pad2)") (class "Default")
      (node (ref "L22") (pin "2") (pinfunction "2_2") (pintype "passive"))
      (node (ref "R87") (pin "2") (pinfunction "2_2") (pintype "passive"))
      (node (ref "R88") (pin "2") (pinfunction "2_2") (pintype "passive"))
    )
    (net (code "41") (name "Net-(L23-Pad2)") (class "Default")
      (node (ref "L23") (pin "2") (pinfunction "2_2") (pintype "passive"))
      (node (ref "R88") (pin "1") (pinfunction "1_1") (pintype "passive"))
      (node (ref "R89") (pin "2") (pinfunction "2_2") (pintype "passive"))
    )
    (net (code "42") (name "Net-(L25-Pad2)") (class "Default")
      (node (ref "L25") (pin "2") (pinfunction "2_2") (pintype "passive"))
      (node (ref "R92") (pin "2") (pinfunction "2_2") (pintype "passive"))
      (node (ref "R94") (pin "2") (pinfunction "2_2") (pintype "passive"))
    )
    (net (code "43") (name "Net-(L26-Pad2)") (class "Default")
      (node (ref "L26") (pin "2") (pinfunction "2_2") (pintype "passive"))
      (node (ref "R94") (pin "1") (pinfunction "1_1") (pintype "passive"))
      (node (ref "R95") (pin "2") (pinfunction "2_2") (pintype "passive"))
    )
    (net (code "44") (name "Net-(L28-Pad2)") (class "Default")
      (node (ref "L28") (pin "2") (pinfunction "2_2") (pintype "passive"))
      (node (ref "R101") (pin "2") (pinfunction "2_2") (pintype "passive"))
      (node (ref "R103") (pin "2") (pinfunction "2_2") (pintype "passive"))
    )
    (net (code "45") (name "Net-(L29-Pad2)") (class "Default")
      (node (ref "L29") (pin "2") (pinfunction "2_2") (pintype "passive"))
      (node (ref "R103") (pin "1") (pinfunction "1_1") (pintype "passive"))
      (node (ref "R104") (pin "2") (pinfunction "2_2") (pintype "passive"))
    )
    (net (code "46") (name "Net-(L31-Pad2)") (class "Default")
      (node (ref "L31") (pin "2") (pinfunction "2_2") (pintype "passive"))
      (node (ref "R109") (pin "2") (pinfunction "2_2") (pintype "passive"))
      (node (ref "R110") (pin "2") (pinfunction "2_2") (pintype "passive"))
    )
    (net (code "47") (name "Net-(L32-Pad2)") (class "Default")
      (node (ref "L32") (pin "2") (pinfunction "2_2") (pintype "passive"))
      (node (ref "R110") (pin "1") (pinfunction "1_1") (pintype "passive"))
      (node (ref "R111") (pin "2") (pinfunction "2_2") (pintype "passive"))
    )
    (net (code "48") (name "Net-(Q9-PadB)") (class "Default")
      (node (ref "Q9") (pin "B") (pintype "passive"))
      (node (ref "R91") (pin "2") (pinfunction "2_2") (pintype "passive"))
      (node (ref "R93") (pin "2") (pinfunction "2_2") (pintype "passive"))
    )
    (net (code "49") (name "Net-(Q10-PadB)") (class "Default")
      (node (ref "Q10") (pin "B") (pintype "passive"))
      (node (ref "R97") (pin "2") (pinfunction "2_2") (pintype "passive"))
      (node (ref "R99") (pin "2") (pinfunction "2_2") (pintype "passive"))
    )
    (net (code "50") (name "Net-(Q11-PadB)") (class "Default")
      (node (ref "Q11") (pin "B") (pintype "passive"))
      (node (ref "R102") (pin "2") (pinfunction "2_2") (pintype "passive"))
      (node (ref "R105") (pin "2") (pinfunction "2_2") (pintype "passive"))
    )
    (net (code "51") (name "Net-(Q12-PadB)") (class "Default")
      (node (ref "Q12") (pin "B") (pintype "passive"))
      (node (ref "R107") (pin "2") (pinfunction "2_2") (pintype "passive"))
      (node (ref "R108") (pin "2") (pinfunction "2_2") (pintype "passive"))
    )
    (net (code "52") (name "Net-(U9-IIN1)") (class "Default")
      (node (ref "C94") (pin "1") (pintype "passive"))
      (node (ref "R89") (pin "1") (pinfunction "1_1") (pintype "passive"))
      (node (ref "U9") (pin "12") (pinfunction "IIN1_12") (pintype "passive"))
    )
    (net (code "53") (name "Net-(U9-IIN2)") (class "Default")
      (node (ref "C102") (pin "1") (pintype "passive"))
      (node (ref "R95") (pin "1") (pinfunction "1_1") (pintype "passive"))
      (node (ref "U9") (pin "14") (pinfunction "IIN2_14") (pintype "passive"))
    )
    (net (code "54") (name "Net-(U9-IIP1)") (class "Default")
      (node (ref "C94") (pin "2") (pintype "passive"))
      (node (ref "R87") (pin "1") (pinfunction "1_1") (pintype "passive"))
      (node (ref "U9") (pin "11") (pinfunction "IIP1_11") (pintype "passive"))
    )
    (net (code "55") (name "Net-(U9-IIP2)") (class "Default")
      (node (ref "C102") (pin "2") (pintype "passive"))
      (node (ref "R92") (pin "1") (pinfunction "1_1") (pintype "passive"))
      (node (ref "U9") (pin "13") (pinfunction "IIP2_13") (pintype "passive"))
    )
    (net (code "56") (name "Net-(U9-VDDA)") (class "Default")
      (node (ref "C100") (pin "1") (pintype "passive"))
      (node (ref "C93") (pin "1") (pinfunction "1_1") (pintype "passive"))
      (node (ref "C98") (pin "2") (pintype "passive"))
      (node (ref "U9") (pin "21") (pinfunction "VDDA_21") (pintype "passive"))
    )
    (net (code "57") (name "Net-(U9-VDDD)") (class "Default")
      (node (ref "C91") (pin "1") (pintype "passive"))
      (node (ref "C96") (pin "1") (pintype "passive"))
      (node (ref "C99") (pin "1") (pinfunction "1_1") (pintype "passive"))
      (node (ref "U9") (pin "27") (pinfunction "VDDD_27") (pintype "passive"))
    )
    (net (code "58") (name "Net-(U9-VIN1)") (class "Default")
      (node (ref "C101") (pin "1") (pintype "passive"))
      (node (ref "L24") (pin "2") (pinfunction "2_2") (pintype "passive"))
      (node (ref "R90") (pin "2") (pinfunction "2_2") (pintype "passive"))
      (node (ref "U9") (pin "10") (pinfunction "VIN1_10") (pintype "passive"))
    )
    (net (code "59") (name "Net-(U9-VIP2)") (class "Default")
      (node (ref "C103") (pin "1") (pintype "passive"))
      (node (ref "L27") (pin "2") (pinfunction "2_2") (pintype "passive"))
      (node (ref "R96") (pin "2") (pinfunction "2_2") (pintype "passive"))
      (node (ref "U9") (pin "16") (pinfunction "VIP2_16") (pintype "passive"))
    )
    (net (code "60") (name "Net-(U9-VREF)") (class "Default")
      (node (ref "C104") (pin "1") (pintype "passive"))
      (node (ref "C105") (pin "1") (pintype "passive"))
      (node (ref "U9") (pin "19") (pinfunction "VREF_19") (pintype "passive"))
    )
    (net (code "61") (name "Net-(U9-VREF1)") (class "Default")
      (node (ref "C106") (pin "1") (pintype "passive"))
      (node (ref "C107") (pin "1") (pintype "passive"))
      (node (ref "U9") (pin "17") (pinfunction "VREF1_17") (pintype "passive"))
    )
    (net (code "62") (name "Net-(U10-IIN1)") (class "Default")
      (node (ref "C114") (pin "1") (pintype "passive"))
      (node (ref "R104") (pin "1") (pinfunction "1_1") (pintype "passive"))
      (node (ref "U10") (pin "12") (pinfunction "IIN1_12") (pintype "passive"))
    )
    (net (code "63") (name "Net-(U10-IIN2)") (class "Default")
      (node (ref "C119") (pin "1") (pintype "passive"))
      (node (ref "R111") (pin "1") (pinfunction "1_1") (pintype "passive"))
      (node (ref "U10") (pin "14") (pinfunction "IIN2_14") (pintype "passive"))
    )
    (net (code "64") (name "Net-(U10-IIP1)") (class "Default")
      (node (ref "C114") (pin "2") (pintype "passive"))
      (node (ref "R101") (pin "1") (pinfunction "1_1") (pintype "passive"))
      (node (ref "U10") (pin "11") (pinfunction "IIP1_11") (pintype "passive"))
    )
    (net (code "65") (name "Net-(U10-IIP2)") (class "Default")
      (node (ref "C119") (pin "2") (pintype "passive"))
      (node (ref "R109") (pin "1") (pinfunction "1_1") (pintype "passive"))
      (node (ref "U10") (pin "13") (pinfunction "IIP2_13") (pintype "passive"))
    )
    (net (code "66") (name "Net-(U10-VDDA)") (class "Default")
      (node (ref "C111") (pin "1") (pinfunction "1_1") (pintype "passive"))
      (node (ref "C115") (pin "1") (pintype "passive"))
      (node (ref "C116") (pin "1") (pintype "passive"))
      (node (ref "U10") (pin "21") (pinfunction "VDDA_21") (pintype "passive"))
    )
    (net (code "67") (name "Net-(U10-VDDD)") (class "Default")
      (node (ref "C112") (pin "1") (pintype "passive"))
      (node (ref "C113") (pin "1") (pintype "passive"))
      (node (ref "C117") (pin "1") (pinfunction "1_1") (pintype "passive"))
      (node (ref "U10") (pin "27") (pinfunction "VDDD_27") (pintype "passive"))
    )
    (net (code "68") (name "Net-(U10-VIN1)") (class "Default")
      (node (ref "C118") (pin "1") (pintype "passive"))
      (node (ref "L30") (pin "2") (pinfunction "2_2") (pintype "passive"))
      (node (ref "R106") (pin "2") (pinfunction "2_2") (pintype "passive"))
      (node (ref "U10") (pin "10") (pinfunction "VIN1_10") (pintype "passive"))
    )
    (net (code "69") (name "Net-(U10-VIP2)") (class "Default")
      (node (ref "C120") (pin "1") (pintype "passive"))
      (node (ref "L33") (pin "2") (pinfunction "2_2") (pintype "passive"))
      (node (ref "R112") (pin "2") (pinfunction "2_2") (pintype "passive"))
      (node (ref "U10") (pin "16") (pinfunction "VIP2_16") (pintype "passive"))
    )
    (net (code "70") (name "Net-(U10-VREF)") (class "Default")
      (node (ref "C121") (pin "1") (pintype "passive"))
      (node (ref "C123") (pin "1") (pintype "passive"))
      (node (ref "U10") (pin "19") (pinfunction "VREF_19") (pintype "passive"))
    )
    (net (code "71") (name "Net-(U10-VREF1)") (class "Default")
      (node (ref "C122") (pin "1") (pintype "passive"))
      (node (ref "C124") (pin "1") (pintype "passive"))
      (node (ref "U10") (pin "17") (pinfunction "VREF1_17") (pintype "passive"))
    )
    (net (code "72") (name "Net-(U10-XTAL2)") (class "Default")
      (node (ref "U10") (pin "2") (pinfunction "XTAL2_2") (pintype "passive"))
      (node (ref "U9") (pin "1") (pinfunction "CLKOUT_1") (pintype "passive"))
    )
    (net (code "73") (name "VCC=3.3V") (class "Default")
      (node (ref "C108") (pin "1") (pintype "passive"))
      (node (ref "C110") (pin "1") (pintype "passive"))
      (node (ref "C95") (pin "1") (pintype "passive"))
      (node (ref "C97") (pin "1") (pintype "passive"))
      (node (ref "M1") (pin "10") (pinfunction "Vin_10") (pintype "passive"))
      (node (ref "R100") (pin "2") (pinfunction "2_2") (pintype "passive"))
      (node (ref "R113") (pin "2") (pinfunction "2_2") (pintype "passive"))
      (node (ref "R114") (pin "2") (pinfunction "2_2") (pintype "passive"))
      (node (ref "R98") (pin "2") (pinfunction "2_2") (pintype "passive"))
      (node (ref "U10") (pin "23") (pinfunction "VCC_23") (pintype "passive"))
      (node (ref "U9") (pin "23") (pinfunction "VCC_23") (pintype "passive"))
    )
    (net (code "74") (name "unconnected-(M1-NC-Pad9)") (class "Default")
      (node (ref "M1") (pin "9") (pinfunction "NC_9") (pintype "passive"))
    )
    (net (code "75") (name "unconnected-(R97-Pad1)") (class "Default")
      (node (ref "R97") (pin "1") (pinfunction "1_1") (pintype "passive"))
    )
    (net (code "76") (name "unconnected-(R102-Pad1)") (class "Default")
      (node (ref "R102") (pin "1") (pinfunction "1_1") (pintype "passive"))
    )
    (net (code "77") (name "unconnected-(R107-Pad1)") (class "Default")
      (node (ref "R107") (pin "1") (pinfunction "1_1") (pintype "passive"))
    )
    (net (code "78") (name "unconnected-(U9-INT1-Pad6)") (class "Default")
      (node (ref "U9") (pin "6") (pinfunction "INT1_6") (pintype "passive"))
    )
    (net (code "79") (name "unconnected-(U9-INT2-Pad7)") (class "Default")
      (node (ref "U9") (pin "7") (pinfunction "INT2_7") (pintype "passive"))
    )
    (net (code "80") (name "unconnected-(U9-NC-Pad24)") (class "Default")
      (node (ref "U9") (pin "24") (pinfunction "NC_24") (pintype "passive"))
    )
    (net (code "81") (name "unconnected-(U9-SYN-Pad28)") (class "Default")
      (node (ref "U9") (pin "28") (pinfunction "SYN_28") (pintype "passive"))
    )
    (net (code "82") (name "unconnected-(U9-XTAL1-Pad3)") (class "Default")
      (node (ref "U9") (pin "3") (pinfunction "XTAL1_3") (pintype "passive"))
    )
    (net (code "83") (name "unconnected-(U10-CLKOUT-Pad1)") (class "Default")
      (node (ref "U10") (pin "1") (pinfunction "CLKOUT_1") (pintype "passive"))
    )
    (net (code "84") (name "unconnected-(U10-INT1-Pad6)") (class "Default")
      (node (ref "U10") (pin "6") (pinfunction "INT1_6") (pintype "passive"))
    )
    (net (code "85") (name "unconnected-(U10-INT2-Pad7)") (class "Default")
      (node (ref "U10") (pin "7") (pinfunction "INT2_7") (pintype "passive"))
    )
    (net (code "86") (name "unconnected-(U10-NC-Pad24)") (class "Default")
      (node (ref "U10") (pin "24") (pinfunction "NC_24") (pintype "passive"))
    )
    (net (code "87") (name "unconnected-(U10-SYN-Pad28)") (class "Default")
      (node (ref "U10") (pin "28") (pinfunction "SYN_28") (pintype "passive"))
    )
    (net (code "88") (name "unconnected-(U10-XTAL1-Pad3)") (class "Default")
      (node (ref "U10") (pin "3") (pinfunction "XTAL1_3") (pintype "passive"))
    )
  )
)
